# 808.net
KiCad netlist of a schematic drawn in EAGLE
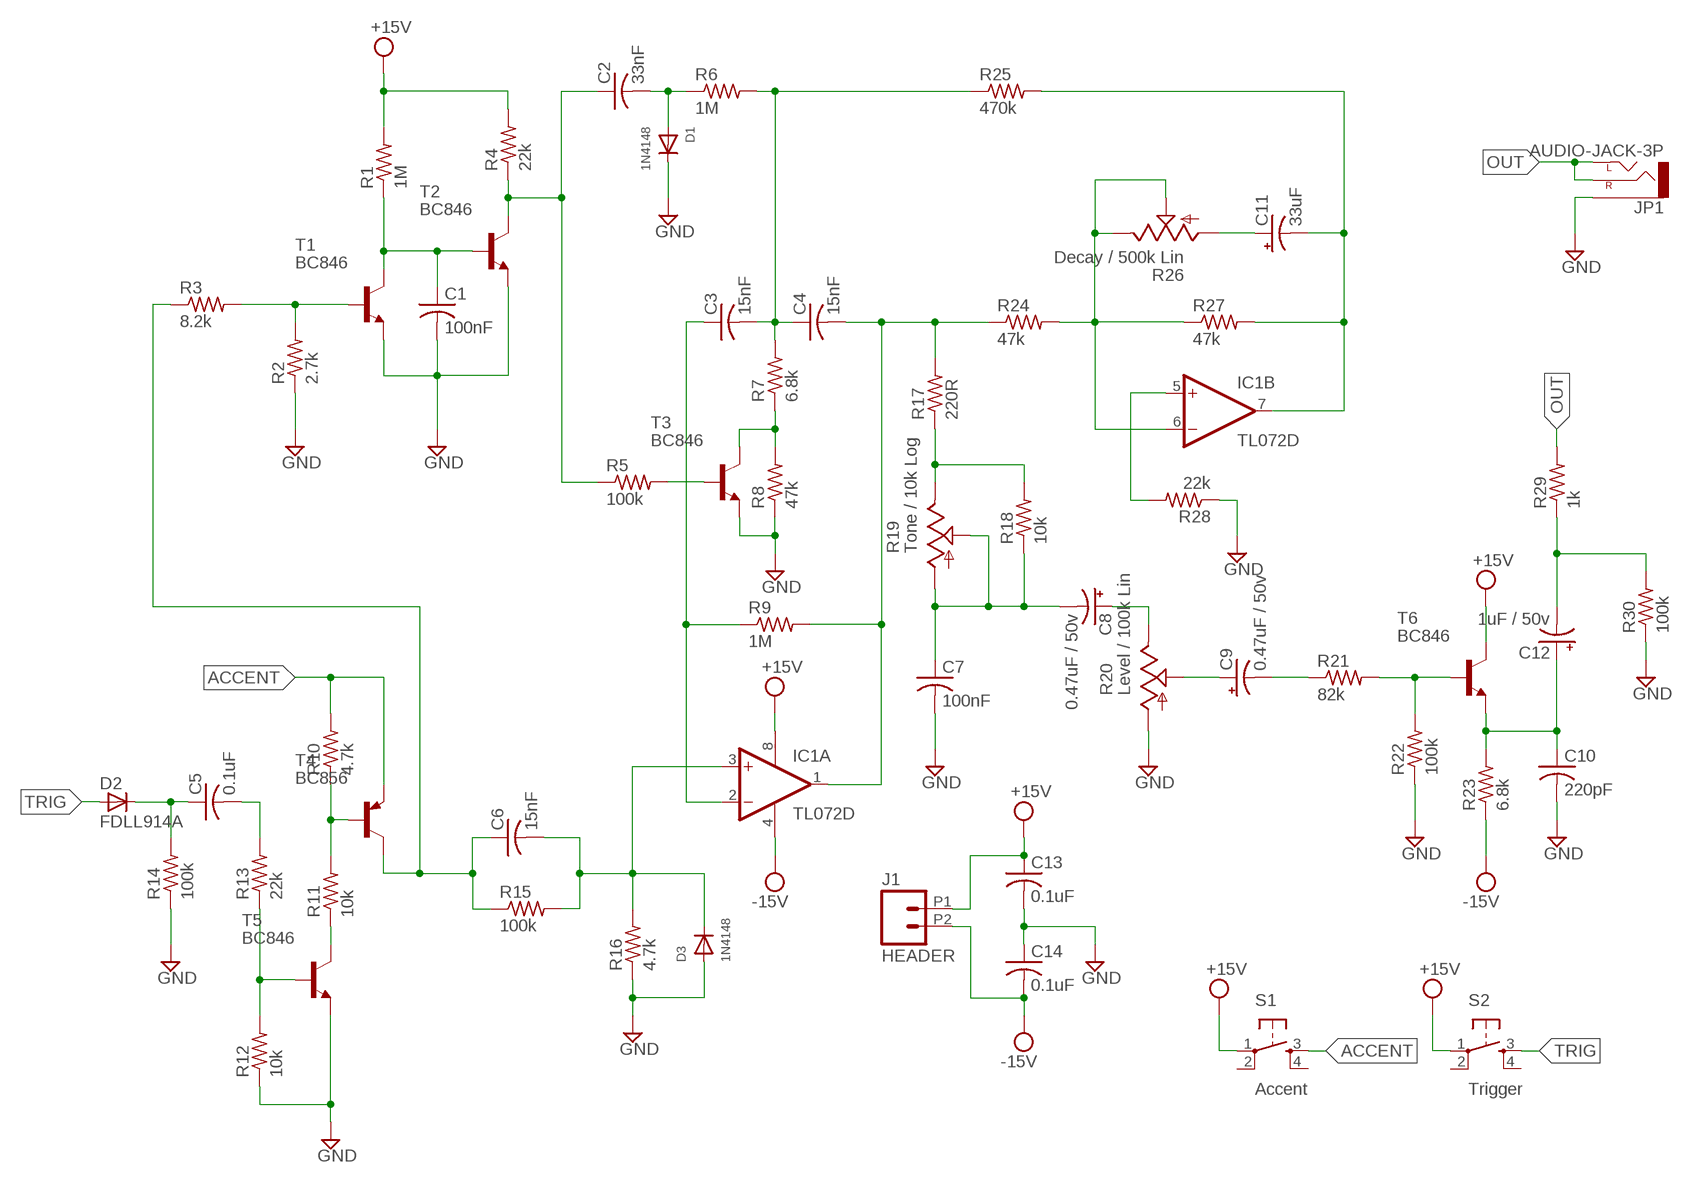
[diagram p0: schematic, sheet 1]

(export (version "E")
  (design (tool "Eeschema 10.0.6"))
  (components
    (comp (ref "C1")
      (value "100nF")
      (footprint "eagle-import:C0805")
      (fields (field (name "PARTNO") "C0805C104K5RACTU"))
      (libsource (lib "eagle-import") (part "C-USC0805"))
    )
    (comp (ref "C2")
      (value "33nF")
      (footprint "eagle-import:C0805")
      (fields (field (name "PARTNO") "CL21B333KBANNNC"))
      (libsource (lib "eagle-import") (part "C-USC0805"))
    )
    (comp (ref "C3")
      (value "15nF")
      (footprint "eagle-import:C0805")
      (fields (field (name "PARTNO") "CC0805KRX7R9BB153"))
      (libsource (lib "eagle-import") (part "C-USC0805"))
    )
    (comp (ref "C4")
      (value "15nF")
      (footprint "eagle-import:C0805")
      (fields (field (name "PARTNO") "CC0805KRX7R9BB153"))
      (libsource (lib "eagle-import") (part "C-USC0805"))
    )
    (comp (ref "C5")
      (value "0.1uF")
      (footprint "eagle-import:C0805")
      (fields (field (name "PARTNO") "C0805C104K5RACTU"))
      (libsource (lib "eagle-import") (part "C-USC0805"))
    )
    (comp (ref "C6")
      (value "15nF")
      (footprint "eagle-import:C0805")
      (fields (field (name "PARTNO") "CC0805KRX7R9BB153"))
      (libsource (lib "eagle-import") (part "C-USC0805"))
    )
    (comp (ref "C7")
      (value "100nF")
      (footprint "eagle-import:C0805")
      (fields (field (name "PARTNO") "C0805C104K5RACTU"))
      (libsource (lib "eagle-import") (part "C-USC0805"))
    )
    (comp (ref "C8")
      (value "0.47uF / 50v")
      (footprint "eagle-import:PANASONIC_VS_B-2")
      (fields (field (name "PARTNO") "EEE-1HAR47AR"))
      (libsource (lib "eagle-import") (part "CAP-POLPANASONIC_B-2"))
    )
    (comp (ref "C9")
      (value "0.47uF / 50v")
      (footprint "eagle-import:PANASONIC_VS_B-2")
      (fields (field (name "PARTNO") "EEE-1HAR47AR"))
      (libsource (lib "eagle-import") (part "CAP-POLPANASONIC_B-2"))
    )
    (comp (ref "C10")
      (value "220pF")
      (footprint "eagle-import:C0805")
      (fields (field (name "PARTNO") "CC0805KRX7R9BB221"))
      (libsource (lib "eagle-import") (part "C-USC0805"))
    )
    (comp (ref "C11")
      (value "33uF")
      (footprint "eagle-import:PANASONIC_VS_B-2")
      (fields (field (name "PARTNO") "EEE-1AA330WAR"))
      (libsource (lib "eagle-import") (part "CAP-POLPANASONIC_B-2"))
    )
    (comp (ref "C12")
      (value "1uF / 50v")
      (footprint "eagle-import:PANASONIC_VS_B-2")
      (fields (field (name "PARTNO") "EEE-1HA010SR"))
      (libsource (lib "eagle-import") (part "CAP-POLPANASONIC_B-2"))
    )
    (comp (ref "C13")
      (value "0.1uF")
      (footprint "eagle-import:C0805")
      (fields (field (name "PARTNO") "C0805C104K5RACTU"))
      (libsource (lib "eagle-import") (part "C-USC0805"))
    )
    (comp (ref "C14")
      (value "0.1uF")
      (footprint "eagle-import:C0805")
      (fields (field (name "PARTNO") "C0805C104K5RACTU"))
      (libsource (lib "eagle-import") (part "C-USC0805"))
    )
    (comp (ref "D1")
      (value "1N4148")
      (footprint "eagle-import:SOD-323F")
      (fields (field (name "PARTNO") "1N4148WS"))
      (libsource (lib "eagle-import") (part "DIODESOD-323F"))
    )
    (comp (ref "D2")
      (value "FDLL914A")
      (footprint "eagle-import:MELF-MLL34")
      (libsource (lib "eagle-import") (part "D-MLL-34"))
    )
    (comp (ref "D3")
      (value "1N4148")
      (footprint "eagle-import:SOD-323F")
      (fields (field (name "PARTNO") "1N4148WS"))
      (libsource (lib "eagle-import") (part "DIODESOD-323F"))
    )
    (comp (ref "IC1")
      (value "TL072D")
      (footprint "eagle-import:SO08")
      (fields (field (name "PARTNO") "TL072SG-13"))
      (libsource (lib "eagle-import") (part "TL072D"))
    )
    (comp (ref "J1")
      (value "HEADER")
      (footprint "eagle-import:1X02-5.08-SCREWTERM")
      (libsource (lib "eagle-import") (part "HEADER"))
    )
    (comp (ref "JP1")
      (value "AUDIO-JACK-3P")
      (footprint "eagle-import:CUI-352X-SMT")
      (fields (field (name "PARTNO") "SJ-3523-SMT-TR"))
      (libsource (lib "eagle-import") (part "AUDIO-JACK-3P"))
    )
    (comp (ref "R1")
      (value "1M")
      (footprint "eagle-import:R0805")
      (fields (field (name "PARTNO") "RC2012F105CS"))
      (libsource (lib "eagle-import") (part "R-US_R0805"))
    )
    (comp (ref "R2")
      (value "2.7k")
      (footprint "eagle-import:R0805")
      (fields (field (name "PARTNO") "RMCF0805JT2K70"))
      (libsource (lib "eagle-import") (part "R-US_R0805"))
    )
    (comp (ref "R3")
      (value "8.2k")
      (footprint "eagle-import:R0805")
      (fields (field (name "PARTNO") "RMCF0805JT8K20"))
      (libsource (lib "eagle-import") (part "R-US_R0805"))
    )
    (comp (ref "R4")
      (value "22k")
      (footprint "eagle-import:R0805")
      (fields (field (name "PARTNO") "RMCF0805JT22K0"))
      (libsource (lib "eagle-import") (part "R-US_R0805"))
    )
    (comp (ref "R5")
      (value "100k")
      (footprint "eagle-import:R0805")
      (fields (field (name "PARTNO") "RC2012J104CS"))
      (libsource (lib "eagle-import") (part "R-US_R0805"))
    )
    (comp (ref "R6")
      (value "1M")
      (footprint "eagle-import:R0805")
      (fields (field (name "PARTNO") "RC2012F105CS"))
      (libsource (lib "eagle-import") (part "R-US_R0805"))
    )
    (comp (ref "R7")
      (value "6.8k")
      (footprint "eagle-import:R0805")
      (fields (field (name "PARTNO") "MCR10ERTF6801"))
      (libsource (lib "eagle-import") (part "R-US_R0805"))
    )
    (comp (ref "R8")
      (value "47k")
      (footprint "eagle-import:R0805")
      (fields (field (name "PARTNO") "RMCF0805JT47K0"))
      (libsource (lib "eagle-import") (part "R-US_R0805"))
    )
    (comp (ref "R9")
      (value "1M")
      (footprint "eagle-import:R0805")
      (fields (field (name "PARTNO") "RC2012F105CS"))
      (libsource (lib "eagle-import") (part "R-US_R0805"))
    )
    (comp (ref "R10")
      (value "4.7k")
      (footprint "eagle-import:R0805")
      (fields (field (name "PARTNO") "RMCF0805JT4K70"))
      (libsource (lib "eagle-import") (part "R-US_R0805"))
    )
    (comp (ref "R11")
      (value "10k")
      (footprint "eagle-import:R0805")
      (fields (field (name "PARTNO") "RC2012J103CS"))
      (libsource (lib "eagle-import") (part "R-US_R0805"))
    )
    (comp (ref "R12")
      (value "10k")
      (footprint "eagle-import:R0805")
      (fields (field (name "PARTNO") "RC2012J103CS"))
      (libsource (lib "eagle-import") (part "R-US_R0805"))
    )
    (comp (ref "R13")
      (value "22k")
      (footprint "eagle-import:R0805")
      (fields (field (name "PARTNO") "RMCF0805JT22K0"))
      (libsource (lib "eagle-import") (part "R-US_R0805"))
    )
    (comp (ref "R14")
      (value "100k")
      (footprint "eagle-import:R0805")
      (fields (field (name "PARTNO") "RC2012J104CS"))
      (libsource (lib "eagle-import") (part "R-US_R0805"))
    )
    (comp (ref "R15")
      (value "100k")
      (footprint "eagle-import:R0805")
      (fields (field (name "PARTNO") "RC2012J104CS"))
      (libsource (lib "eagle-import") (part "R-US_R0805"))
    )
    (comp (ref "R16")
      (value "4.7k")
      (footprint "eagle-import:R0805")
      (fields (field (name "PARTNO") "RMCF0805JT4K70"))
      (libsource (lib "eagle-import") (part "R-US_R0805"))
    )
    (comp (ref "R17")
      (value "220R")
      (footprint "eagle-import:R0805")
      (fields (field (name "PARTNO") "RMCF0805JT220R"))
      (libsource (lib "eagle-import") (part "R-US_R0805"))
    )
    (comp (ref "R18")
      (value "10k")
      (footprint "eagle-import:R0805")
      (fields (field (name "PARTNO") "RC2012J103CS"))
      (libsource (lib "eagle-import") (part "R-US_R0805"))
    )
    (comp (ref "R19")
      (value "Tone / 10k Log")
      (footprint "eagle-import:POTENTIOMETER-PTV09")
      (fields (field (name "PARTNO") "PTV09A-4020F-A103"))
      (libsource (lib "eagle-import") (part "POTPTV09-H"))
    )
    (comp (ref "R20")
      (value "Level / 100k Lin")
      (footprint "eagle-import:POTENTIOMETER-CTS296")
      (fields (field (name "PARTNO") "296UD104B1N"))
      (libsource (lib "eagle-import") (part "POTCTS296"))
    )
    (comp (ref "R21")
      (value "82k")
      (footprint "eagle-import:R0805")
      (fields (field (name "PARTNO") "RMCF0805JT82K0"))
      (libsource (lib "eagle-import") (part "R-US_R0805"))
    )
    (comp (ref "R22")
      (value "100k")
      (footprint "eagle-import:R0805")
      (fields (field (name "PARTNO") "RC2012J104CS"))
      (libsource (lib "eagle-import") (part "R-US_R0805"))
    )
    (comp (ref "R23")
      (value "6.8k")
      (footprint "eagle-import:R0805")
      (fields (field (name "PARTNO") "MCR10ERTF6801"))
      (libsource (lib "eagle-import") (part "R-US_R0805"))
    )
    (comp (ref "R24")
      (value "47k")
      (footprint "eagle-import:R0805")
      (fields (field (name "PARTNO") "RMCF0805JT47K0"))
      (libsource (lib "eagle-import") (part "R-US_R0805"))
    )
    (comp (ref "R25")
      (value "470k")
      (footprint "eagle-import:R0805")
      (fields (field (name "PARTNO") "RMCF0805JT470K"))
      (libsource (lib "eagle-import") (part "R-US_R0805"))
    )
    (comp (ref "R26")
      (value "Decay / 500k Lin")
      (footprint "eagle-import:POTENTIOMETER-PTV09")
      (fields (field (name "PARTNO") "296UD504B1N"))
      (libsource (lib "eagle-import") (part "POTPTV09-H"))
    )
    (comp (ref "R27")
      (value "47k")
      (footprint "eagle-import:R0805")
      (fields (field (name "PARTNO") "RMCF0805JT47K0"))
      (libsource (lib "eagle-import") (part "R-US_R0805"))
    )
    (comp (ref "R28")
      (value "22k")
      (footprint "eagle-import:R0805")
      (fields (field (name "PARTNO") "RMCF0805JT22K0"))
      (libsource (lib "eagle-import") (part "R-US_R0805"))
    )
    (comp (ref "R29")
      (value "1k")
      (footprint "eagle-import:R0805")
      (fields (field (name "PARTNO") "RC2012J102CS"))
      (libsource (lib "eagle-import") (part "R-US_R0805"))
    )
    (comp (ref "R30")
      (value "100k")
      (footprint "eagle-import:R0805")
      (fields (field (name "PARTNO") "RC2012J104CS"))
      (libsource (lib "eagle-import") (part "R-US_R0805"))
    )
    (comp (ref "S1")
      (value "Accent")
      (footprint "eagle-import:TACTILE-SWITCH-SMD")
      (fields (field (name "PARTNO") "PTS525SM10SMTR LFS"))
      (libsource (lib "eagle-import") (part "TAC_SWITCHSMD"))
    )
    (comp (ref "S2")
      (value "Trigger")
      (footprint "eagle-import:TACTILE-SWITCH-SMD")
      (fields (field (name "PARTNO") "PTS525SM10SMTR LFS"))
      (libsource (lib "eagle-import") (part "TAC_SWITCHSMD"))
    )
    (comp (ref "T1")
      (value "BC846")
      (footprint "eagle-import:SOT23")
      (fields (field (name "PARTNO") "BC846BMTF"))
      (libsource (lib "eagle-import") (part "BC846"))
    )
    (comp (ref "T2")
      (value "BC846")
      (footprint "eagle-import:SOT23")
      (fields (field (name "PARTNO") "BC846BMTF"))
      (libsource (lib "eagle-import") (part "BC846"))
    )
    (comp (ref "T3")
      (value "BC846")
      (footprint "eagle-import:SOT23")
      (fields (field (name "PARTNO") "BC846BMTF"))
      (libsource (lib "eagle-import") (part "BC846"))
    )
    (comp (ref "T4")
      (value "BC856")
      (footprint "eagle-import:SOT23-BEC")
      (fields (field (name "PARTNO") "BC856BMTF"))
      (libsource (lib "eagle-import") (part "-PNP-SOT23-BECBC856B"))
    )
    (comp (ref "T5")
      (value "BC846")
      (footprint "eagle-import:SOT23")
      (fields (field (name "PARTNO") "BC846BMTF"))
      (libsource (lib "eagle-import") (part "BC846"))
    )
    (comp (ref "T6")
      (value "BC846")
      (footprint "eagle-import:SOT23")
      (fields (field (name "PARTNO") "BC846BMTF"))
      (libsource (lib "eagle-import") (part "BC846"))
    )
  )
  (nets
    (net (code "1") (name "+15V") (class "Default")
      (node (ref "C13") (pin "1") (pinfunction "1_1") (pintype "passive"))
      (node (ref "IC1") (pin "8") (pinfunction "V+_8") (pintype "power_in"))
      (node (ref "J1") (pin "P1") (pinfunction "2_P1") (pintype "passive"))
      (node (ref "R1") (pin "2") (pinfunction "2_2") (pintype "passive"))
      (node (ref "R4") (pin "2") (pinfunction "2_2") (pintype "passive"))
      (node (ref "S1") (pin "1") (pinfunction "1_1") (pintype "passive"))
      (node (ref "S2") (pin "1") (pinfunction "1_1") (pintype "passive"))
      (node (ref "T6") (pin "3") (pinfunction "C_3") (pintype "passive"))
    )
    (net (code "2") (name "-15V") (class "Default")
      (node (ref "C14") (pin "2") (pinfunction "2_2") (pintype "passive"))
      (node (ref "IC1") (pin "4") (pinfunction "V-_4") (pintype "power_in"))
      (node (ref "J1") (pin "P2") (pinfunction "1_P2") (pintype "passive"))
      (node (ref "R23") (pin "1") (pinfunction "1_1") (pintype "passive"))
    )
    (net (code "3") (name "ACCENT") (class "Default")
      (node (ref "R10") (pin "2") (pinfunction "2_2") (pintype "passive"))
      (node (ref "S1") (pin "3") (pinfunction "3_3") (pintype "passive"))
      (node (ref "T4") (pin "E") (pinfunction "E_E") (pintype "passive"))
    )
    (net (code "4") (name "GND") (class "Default")
      (node (ref "C1") (pin "2") (pinfunction "2_2") (pintype "passive"))
      (node (ref "C10") (pin "2") (pinfunction "2_2") (pintype "passive"))
      (node (ref "C13") (pin "2") (pinfunction "2_2") (pintype "passive"))
      (node (ref "C14") (pin "1") (pinfunction "1_1") (pintype "passive"))
      (node (ref "C7") (pin "2") (pinfunction "2_2") (pintype "passive"))
      (node (ref "D1") (pin "C") (pinfunction "C_C") (pintype "passive"))
      (node (ref "D3") (pin "A") (pinfunction "A_A") (pintype "passive"))
      (node (ref "JP1") (pin "1") (pinfunction "SLEEVE_1") (pintype "bidirectional"))
      (node (ref "R12") (pin "1") (pinfunction "1_1") (pintype "passive"))
      (node (ref "R14") (pin "1") (pinfunction "1_1") (pintype "passive"))
      (node (ref "R16") (pin "1") (pinfunction "1_1") (pintype "passive"))
      (node (ref "R2") (pin "1") (pinfunction "1_1") (pintype "passive"))
      (node (ref "R20") (pin "P$1") (pinfunction "A_P$1") (pintype "passive"))
      (node (ref "R22") (pin "1") (pinfunction "1_1") (pintype "passive"))
      (node (ref "R28") (pin "1") (pinfunction "1_1") (pintype "passive"))
      (node (ref "R30") (pin "1") (pinfunction "1_1") (pintype "passive"))
      (node (ref "R8") (pin "1") (pinfunction "1_1") (pintype "passive"))
      (node (ref "T1") (pin "2") (pinfunction "E_2") (pintype "passive"))
      (node (ref "T2") (pin "2") (pinfunction "E_2") (pintype "passive"))
      (node (ref "T3") (pin "2") (pinfunction "E_2") (pintype "passive"))
      (node (ref "T5") (pin "2") (pinfunction "E_2") (pintype "passive"))
    )
    (net (code "5") (name "Net-(C2-Pad2)") (class "Default")
      (node (ref "C2") (pin "2") (pinfunction "2_2") (pintype "passive"))
      (node (ref "D1") (pin "A") (pinfunction "A_A") (pintype "passive"))
      (node (ref "R6") (pin "1") (pinfunction "1_1") (pintype "passive"))
    )
    (net (code "6") (name "Net-(C3-Pad2)") (class "Default")
      (node (ref "C3") (pin "2") (pinfunction "2_2") (pintype "passive"))
      (node (ref "C4") (pin "1") (pinfunction "1_1") (pintype "passive"))
      (node (ref "R25") (pin "1") (pinfunction "1_1") (pintype "passive"))
      (node (ref "R6") (pin "2") (pinfunction "2_2") (pintype "passive"))
      (node (ref "R7") (pin "2") (pinfunction "2_2") (pintype "passive"))
    )
    (net (code "7") (name "Net-(C5-Pad2)") (class "Default")
      (node (ref "C5") (pin "2") (pinfunction "2_2") (pintype "passive"))
      (node (ref "R13") (pin "2") (pinfunction "2_2") (pintype "passive"))
    )
    (net (code "8") (name "Net-(C6-Pad1)") (class "Default")
      (node (ref "C6") (pin "1") (pinfunction "1_1") (pintype "passive"))
      (node (ref "R15") (pin "1") (pinfunction "1_1") (pintype "passive"))
      (node (ref "R3") (pin "1") (pinfunction "1_1") (pintype "passive"))
      (node (ref "T4") (pin "C") (pinfunction "C_C") (pintype "passive"))
    )
    (net (code "9") (name "Net-(C9-Pad-)") (class "Default")
      (node (ref "C9") (pin "-") (pinfunction "-_-") (pintype "passive"))
      (node (ref "R21") (pin "1") (pinfunction "1_1") (pintype "passive"))
    )
    (net (code "10") (name "Net-(C12-Pad-)") (class "Default")
      (node (ref "C12") (pin "-") (pinfunction "-_-") (pintype "passive"))
      (node (ref "R29") (pin "1") (pinfunction "1_1") (pintype "passive"))
      (node (ref "R30") (pin "2") (pinfunction "2_2") (pintype "passive"))
    )
    (net (code "11") (name "Net-(D2-C)") (class "Default")
      (node (ref "C5") (pin "1") (pinfunction "1_1") (pintype "passive"))
      (node (ref "D2") (pin "1") (pinfunction "C_1") (pintype "passive"))
      (node (ref "R14") (pin "2") (pinfunction "2_2") (pintype "passive"))
    )
    (net (code "12") (name "Net-(IC1A-+IN)") (class "Default")
      (node (ref "C6") (pin "2") (pinfunction "2_2") (pintype "passive"))
      (node (ref "D3") (pin "C") (pinfunction "C_C") (pintype "passive"))
      (node (ref "IC1") (pin "3") (pinfunction "+IN_3") (pintype "input"))
      (node (ref "R15") (pin "2") (pinfunction "2_2") (pintype "passive"))
      (node (ref "R16") (pin "2") (pinfunction "2_2") (pintype "passive"))
    )
    (net (code "13") (name "Net-(IC1A--IN)") (class "Default")
      (node (ref "C3") (pin "1") (pinfunction "1_1") (pintype "passive"))
      (node (ref "IC1") (pin "2") (pinfunction "-IN_2") (pintype "input"))
      (node (ref "R9") (pin "1") (pinfunction "1_1") (pintype "passive"))
    )
    (net (code "14") (name "Net-(IC1A-OUT)") (class "Default")
      (node (ref "C4") (pin "2") (pinfunction "2_2") (pintype "passive"))
      (node (ref "IC1") (pin "1") (pinfunction "OUT_1") (pintype "output"))
      (node (ref "R17") (pin "2") (pinfunction "2_2") (pintype "passive"))
      (node (ref "R24") (pin "1") (pinfunction "1_1") (pintype "passive"))
      (node (ref "R9") (pin "2") (pinfunction "2_2") (pintype "passive"))
    )
    (net (code "15") (name "Net-(IC1B-+IN)") (class "Default")
      (node (ref "IC1") (pin "5") (pinfunction "+IN_5") (pintype "input"))
      (node (ref "R28") (pin "2") (pinfunction "2_2") (pintype "passive"))
    )
    (net (code "16") (name "Net-(IC1B--IN)") (class "Default")
      (node (ref "IC1") (pin "6") (pinfunction "-IN_6") (pintype "input"))
      (node (ref "R24") (pin "2") (pinfunction "2_2") (pintype "passive"))
      (node (ref "R26") (pin "P$2") (pinfunction "S_P$2") (pintype "passive"))
      (node (ref "R26") (pin "P$3") (pinfunction "E_P$3") (pintype "passive"))
      (node (ref "R27") (pin "1") (pinfunction "1_1") (pintype "passive"))
    )
    (net (code "17") (name "Net-(IC1B-OUT)") (class "Default")
      (node (ref "C11") (pin "-") (pinfunction "-_-") (pintype "passive"))
      (node (ref "IC1") (pin "7") (pinfunction "OUT_7") (pintype "output"))
      (node (ref "R25") (pin "2") (pinfunction "2_2") (pintype "passive"))
      (node (ref "R27") (pin "2") (pinfunction "2_2") (pintype "passive"))
    )
    (net (code "18") (name "Net-(R10-Pad1)") (class "Default")
      (node (ref "R10") (pin "1") (pinfunction "1_1") (pintype "passive"))
      (node (ref "R11") (pin "2") (pinfunction "2_2") (pintype "passive"))
      (node (ref "T4") (pin "B") (pinfunction "B_B") (pintype "passive"))
    )
    (net (code "19") (name "Net-(R19-A)") (class "Default")
      (node (ref "C7") (pin "1") (pinfunction "1_1") (pintype "passive"))
      (node (ref "C8") (pin "-") (pinfunction "-_-") (pintype "passive"))
      (node (ref "R18") (pin "1") (pinfunction "1_1") (pintype "passive"))
      (node (ref "R19") (pin "P$1") (pinfunction "A_P$1") (pintype "passive"))
      (node (ref "R19") (pin "P$2") (pinfunction "S_P$2") (pintype "passive"))
    )
    (net (code "20") (name "Net-(R19-E)") (class "Default")
      (node (ref "R17") (pin "1") (pinfunction "1_1") (pintype "passive"))
      (node (ref "R18") (pin "2") (pinfunction "2_2") (pintype "passive"))
      (node (ref "R19") (pin "P$3") (pinfunction "E_P$3") (pintype "passive"))
    )
    (net (code "21") (name "Net-(R20-E)") (class "Default")
      (node (ref "C8") (pin "+") (pinfunction "+_+") (pintype "passive"))
      (node (ref "R20") (pin "P$3") (pinfunction "E_P$3") (pintype "passive"))
    )
    (net (code "22") (name "Net-(R20-S)") (class "Default")
      (node (ref "C9") (pin "+") (pinfunction "+_+") (pintype "passive"))
      (node (ref "R20") (pin "P$2") (pinfunction "S_P$2") (pintype "passive"))
    )
    (net (code "23") (name "Net-(R26-A)") (class "Default")
      (node (ref "C11") (pin "+") (pinfunction "+_+") (pintype "passive"))
      (node (ref "R26") (pin "P$1") (pinfunction "A_P$1") (pintype "passive"))
    )
    (net (code "24") (name "Net-(T1-B)") (class "Default")
      (node (ref "R2") (pin "2") (pinfunction "2_2") (pintype "passive"))
      (node (ref "R3") (pin "2") (pinfunction "2_2") (pintype "passive"))
      (node (ref "T1") (pin "1") (pinfunction "B_1") (pintype "passive"))
    )
    (net (code "25") (name "Net-(T1-C)") (class "Default")
      (node (ref "C1") (pin "1") (pinfunction "1_1") (pintype "passive"))
      (node (ref "R1") (pin "1") (pinfunction "1_1") (pintype "passive"))
      (node (ref "T1") (pin "3") (pinfunction "C_3") (pintype "passive"))
      (node (ref "T2") (pin "1") (pinfunction "B_1") (pintype "passive"))
    )
    (net (code "26") (name "Net-(T2-C)") (class "Default")
      (node (ref "C2") (pin "1") (pinfunction "1_1") (pintype "passive"))
      (node (ref "R4") (pin "1") (pinfunction "1_1") (pintype "passive"))
      (node (ref "R5") (pin "1") (pinfunction "1_1") (pintype "passive"))
      (node (ref "T2") (pin "3") (pinfunction "C_3") (pintype "passive"))
    )
    (net (code "27") (name "Net-(T3-B)") (class "Default")
      (node (ref "R5") (pin "2") (pinfunction "2_2") (pintype "passive"))
      (node (ref "T3") (pin "1") (pinfunction "B_1") (pintype "passive"))
    )
    (net (code "28") (name "Net-(T3-C)") (class "Default")
      (node (ref "R7") (pin "1") (pinfunction "1_1") (pintype "passive"))
      (node (ref "R8") (pin "2") (pinfunction "2_2") (pintype "passive"))
      (node (ref "T3") (pin "3") (pinfunction "C_3") (pintype "passive"))
    )
    (net (code "29") (name "Net-(T5-B)") (class "Default")
      (node (ref "R12") (pin "2") (pinfunction "2_2") (pintype "passive"))
      (node (ref "R13") (pin "1") (pinfunction "1_1") (pintype "passive"))
      (node (ref "T5") (pin "1") (pinfunction "B_1") (pintype "passive"))
    )
    (net (code "30") (name "Net-(T5-C)") (class "Default")
      (node (ref "R11") (pin "1") (pinfunction "1_1") (pintype "passive"))
      (node (ref "T5") (pin "3") (pinfunction "C_3") (pintype "passive"))
    )
    (net (code "31") (name "Net-(T6-B)") (class "Default")
      (node (ref "R21") (pin "2") (pinfunction "2_2") (pintype "passive"))
      (node (ref "R22") (pin "2") (pinfunction "2_2") (pintype "passive"))
      (node (ref "T6") (pin "1") (pinfunction "B_1") (pintype "passive"))
    )
    (net (code "32") (name "Net-(T6-E)") (class "Default")
      (node (ref "C10") (pin "1") (pinfunction "1_1") (pintype "passive"))
      (node (ref "C12") (pin "+") (pinfunction "+_+") (pintype "passive"))
      (node (ref "R23") (pin "2") (pinfunction "2_2") (pintype "passive"))
      (node (ref "T6") (pin "2") (pinfunction "E_2") (pintype "passive"))
    )
    (net (code "33") (name "OUT") (class "Default")
      (node (ref "JP1") (pin "2") (pinfunction "LEFT_2") (pintype "bidirectional"))
      (node (ref "JP1") (pin "3") (pinfunction "RIGHT_3") (pintype "bidirectional"))
      (node (ref "R29") (pin "2") (pinfunction "2_2") (pintype "passive"))
    )
    (net (code "34") (name "TRIG") (class "Default")
      (node (ref "D2") (pin "2") (pinfunction "A_2") (pintype "passive"))
      (node (ref "S2") (pin "3") (pinfunction "3_3") (pintype "passive"))
    )
    (net (code "35") (name "unconnected-(S1-Pad2)") (class "Default")
      (node (ref "S1") (pin "2") (pinfunction "2_2") (pintype "passive"))
    )
    (net (code "36") (name "unconnected-(S1-Pad4)") (class "Default")
      (node (ref "S1") (pin "4") (pinfunction "4_4") (pintype "passive"))
    )
    (net (code "37") (name "unconnected-(S2-Pad2)") (class "Default")
      (node (ref "S2") (pin "2") (pinfunction "2_2") (pintype "passive"))
    )
    (net (code "38") (name "unconnected-(S2-Pad4)") (class "Default")
      (node (ref "S2") (pin "4") (pinfunction "4_4") (pintype "passive"))
    )
  )
)
